# SguanFOC_MOTOR.net
KiCad netlist of a schematic drawn in EasyEDA Pro
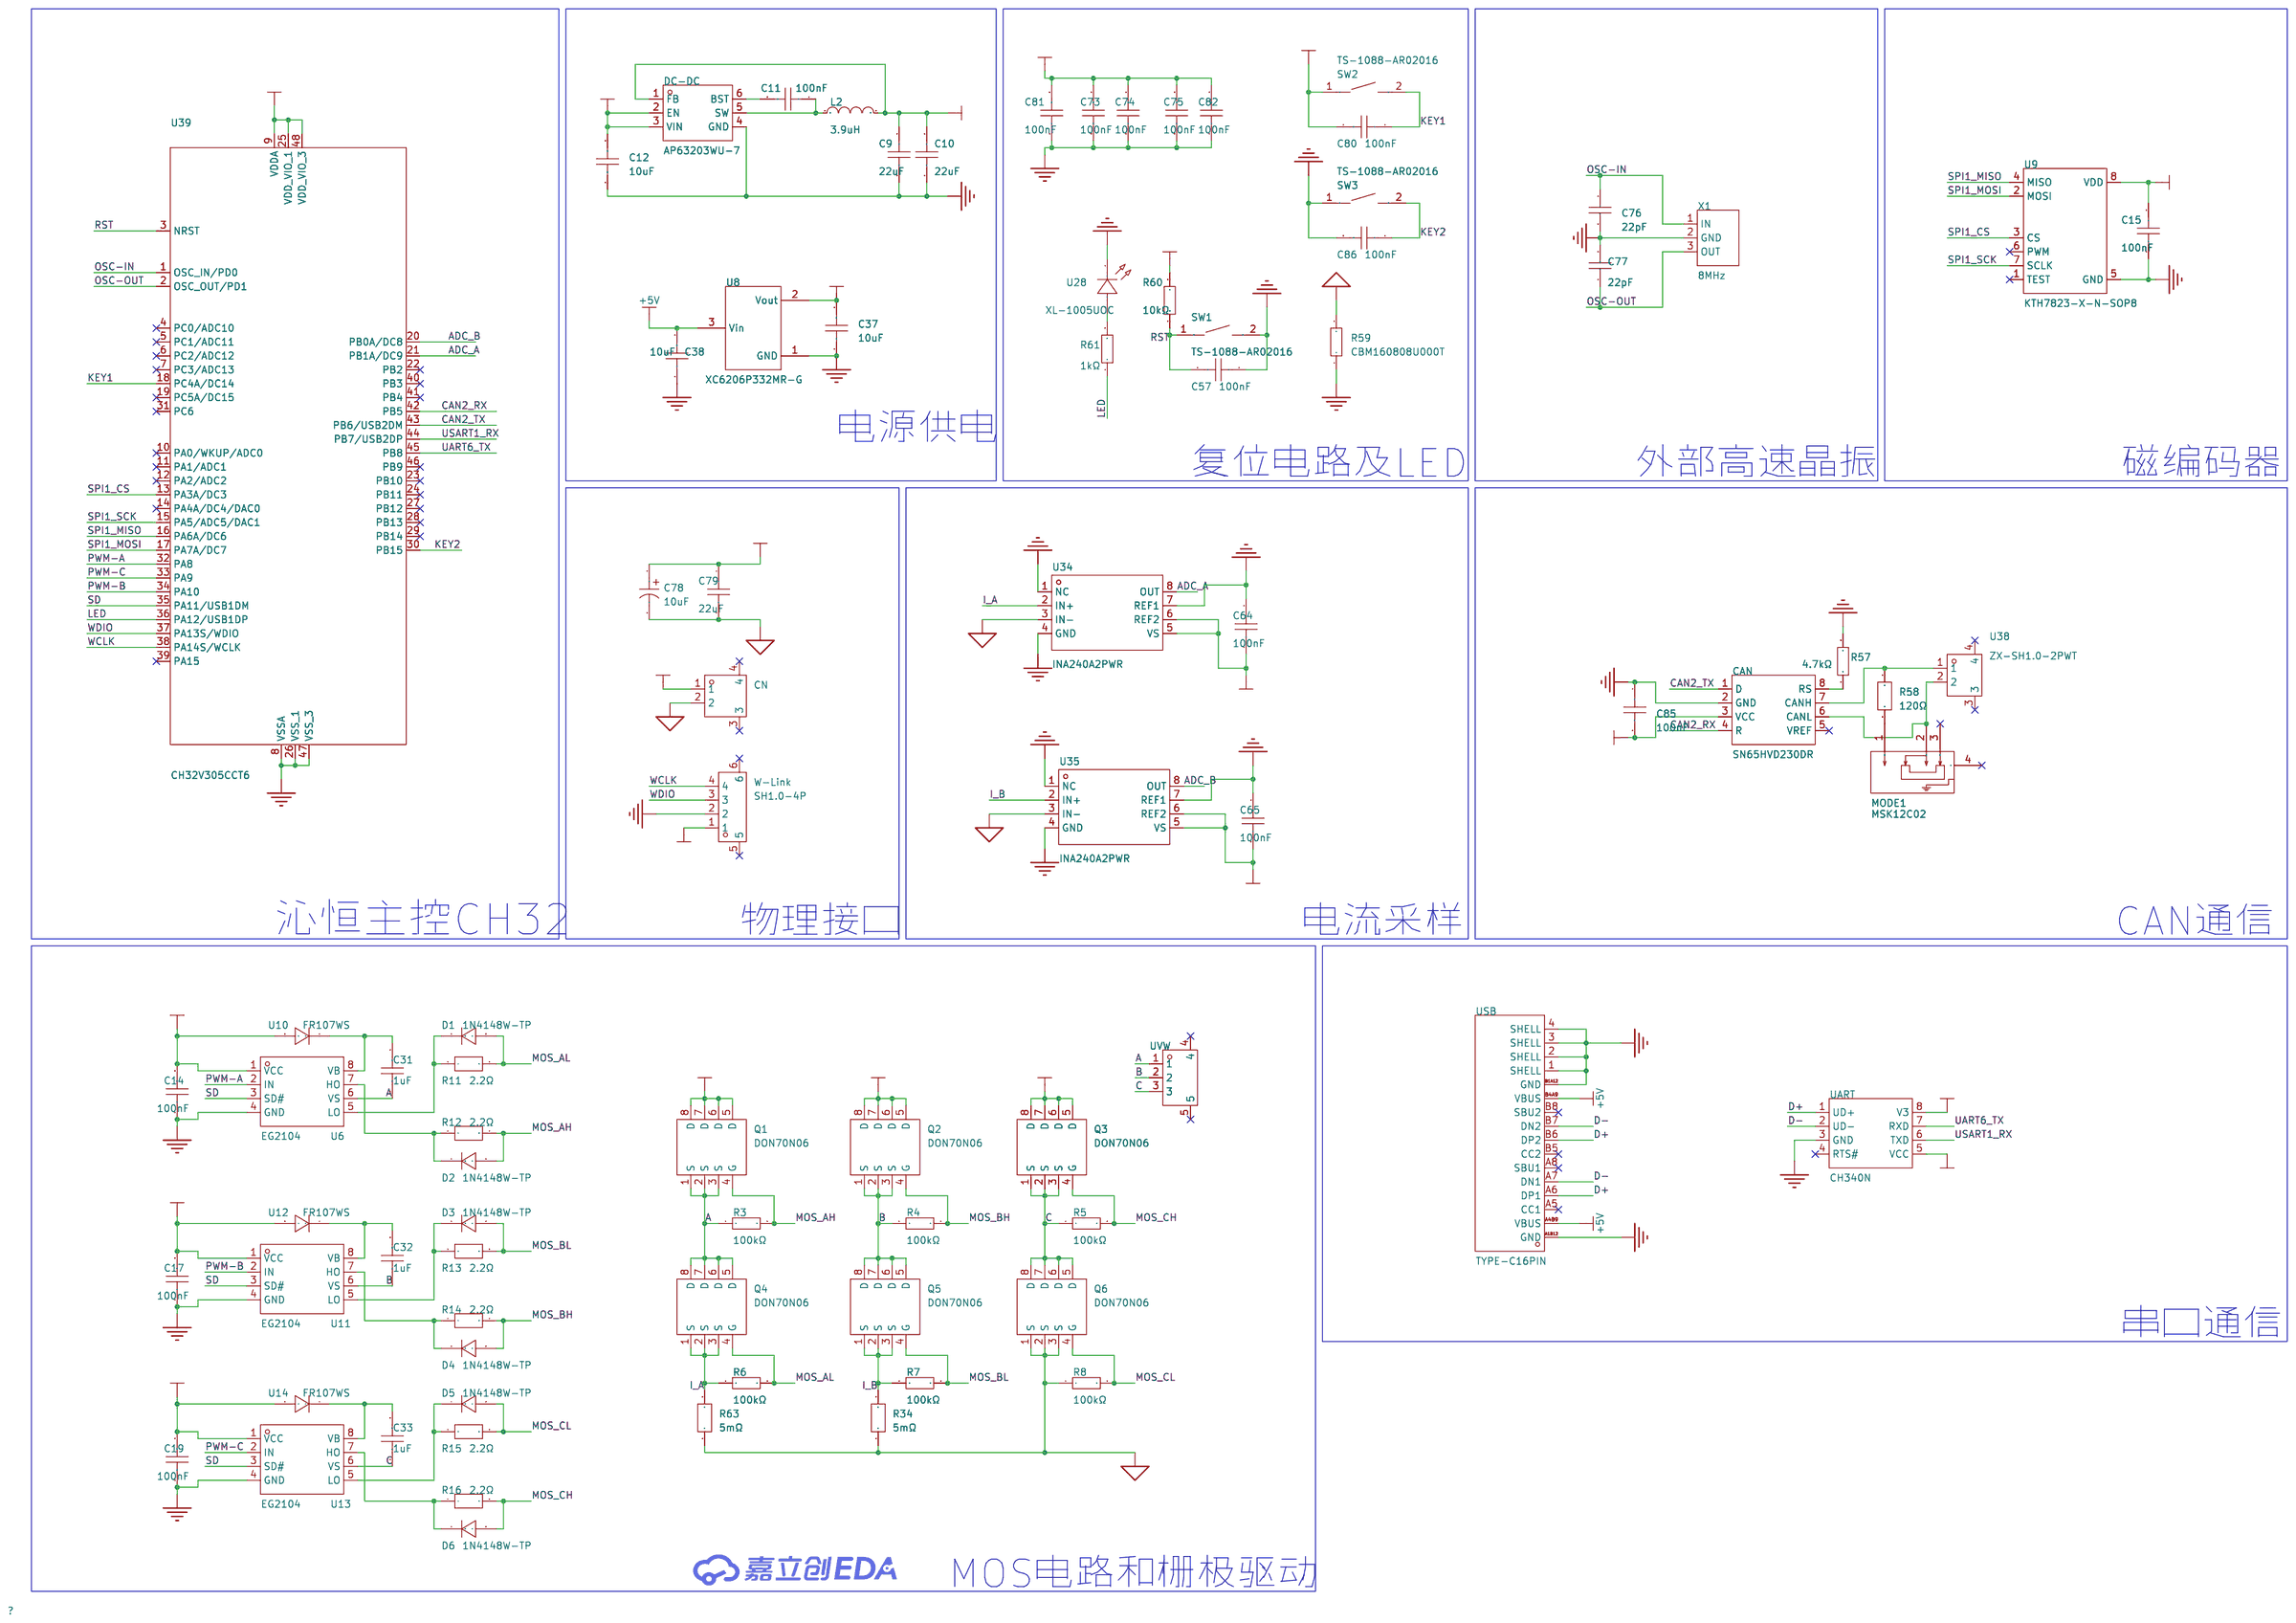
[diagram p0: schematic sheet]

(export (version "E")
  (design (tool "Eeschema 10.0.6"))
  (components
    (comp (ref "C9")
      (value "22uF")
      (footprint "easyedapro:C0603")
      (description "容值:22uF;精度:±20%;额定电压:10V;温度系数:X5R;")
      (fields
        (field (name "Manufacturer Part") "CGA0603X5R226M100JT")
        (field (name "Manufacturer") "HRE(芯声)")
      )
      (libsource (lib "easyedapro") (part "CGA0603X5R226M100JT"))
    )
    (comp (ref "C10")
      (value "22uF")
      (footprint "easyedapro:C0603")
      (description "容值:22uF;精度:±20%;额定电压:10V;温度系数:X5R;")
      (fields
        (field (name "Manufacturer Part") "CGA0603X5R226M100JT")
        (field (name "Manufacturer") "HRE(芯声)")
      )
      (libsource (lib "easyedapro") (part "CGA0603X5R226M100JT"))
    )
    (comp (ref "C11")
      (value "100nF")
      (footprint "easyedapro:C0603")
      (description "容值:100nF;精度:±10%;额定电压:50V;温度系数:X7R;")
      (fields
        (field (name "Manufacturer Part") "CGA0603X7R104K500JT")
        (field (name "Manufacturer") "HRE(芯声)")
      )
      (libsource (lib "easyedapro") (part "CGA0603X7R104K500JT"))
    )
    (comp (ref "C12")
      (value "10uF")
      (footprint "easyedapro:C0603")
      (description "容值:10uF;精度:±10%;额定电压:10V;温度系数:X5R;")
      (fields
        (field (name "Manufacturer Part") "CGA0603X5R106K100JT")
        (field (name "Manufacturer") "HRE(芯声)")
      )
      (libsource (lib "easyedapro") (part "CGA0603X5R106K100JT"))
    )
    (comp (ref "C14")
      (value "100nF")
      (footprint "easyedapro:C0603")
      (description "容值:100nF;精度:±10%;额定电压:50V;温度系数:X7R;")
      (fields
        (field (name "Manufacturer Part") "CGA0603X7R104K500JT")
        (field (name "Manufacturer") "HRE(芯声)")
      )
      (libsource (lib "easyedapro") (part "CGA0603X7R104K500JT"))
    )
    (comp (ref "C15")
      (value "100nF")
      (footprint "easyedapro:C0603")
      (description "容值:100nF;精度:±10%;额定电压:50V;温度系数:X7R;")
      (fields
        (field (name "Manufacturer Part") "CGA0603X7R104K500JT")
        (field (name "Manufacturer") "HRE(芯声)")
      )
      (libsource (lib "easyedapro") (part "CGA0603X7R104K500JT"))
    )
    (comp (ref "C17")
      (value "100nF")
      (footprint "easyedapro:C0603")
      (description "容值:100nF;精度:±10%;额定电压:50V;温度系数:X7R;")
      (fields
        (field (name "Manufacturer Part") "CGA0603X7R104K500JT")
        (field (name "Manufacturer") "HRE(芯声)")
      )
      (libsource (lib "easyedapro") (part "CGA0603X7R104K500JT"))
    )
    (comp (ref "C19")
      (value "100nF")
      (footprint "easyedapro:C0603")
      (description "容值:100nF;精度:±10%;额定电压:50V;温度系数:X7R;")
      (fields
        (field (name "Manufacturer Part") "CGA0603X7R104K500JT")
        (field (name "Manufacturer") "HRE(芯声)")
      )
      (libsource (lib "easyedapro") (part "CGA0603X7R104K500JT"))
    )
    (comp (ref "C31")
      (value "1uF")
      (footprint "easyedapro:C0603")
      (description "容值:1uF;精度:±10%;额定电压:50V;温度系数:X5R;")
      (fields
        (field (name "Manufacturer Part") "CGA0603X5R105K500JT")
        (field (name "Manufacturer") "HRE(芯声)")
      )
      (libsource (lib "easyedapro") (part "CGA0603X5R105K500JT"))
    )
    (comp (ref "C32")
      (value "1uF")
      (footprint "easyedapro:C0603")
      (description "容值:1uF;精度:±10%;额定电压:50V;温度系数:X5R;")
      (fields
        (field (name "Manufacturer Part") "CGA0603X5R105K500JT")
        (field (name "Manufacturer") "HRE(芯声)")
      )
      (libsource (lib "easyedapro") (part "CGA0603X5R105K500JT"))
    )
    (comp (ref "C33")
      (value "1uF")
      (footprint "easyedapro:C0603")
      (description "容值:1uF;精度:±10%;额定电压:50V;温度系数:X5R;")
      (fields
        (field (name "Manufacturer Part") "CGA0603X5R105K500JT")
        (field (name "Manufacturer") "HRE(芯声)")
      )
      (libsource (lib "easyedapro") (part "CGA0603X5R105K500JT"))
    )
    (comp (ref "C37")
      (value "10uF")
      (footprint "easyedapro:C0603")
      (libsource (lib "easyedapro") (part "Capacitance"))
    )
    (comp (ref "C38")
      (value "10uF")
      (footprint "easyedapro:C0603")
      (libsource (lib "easyedapro") (part "Capacitance"))
    )
    (comp (ref "C57")
      (value "100nF")
      (footprint "easyedapro:C0603")
      (description "容值:100nF;精度:±10%;额定电压:50V;温度系数:X7R;")
      (fields
        (field (name "Manufacturer Part") "CGA0603X7R104K500JT")
        (field (name "Manufacturer") "HRE(芯声)")
      )
      (libsource (lib "easyedapro") (part "CGA0603X7R104K500JT"))
    )
    (comp (ref "C64")
      (value "100nF")
      (footprint "easyedapro:C0603")
      (description "容值:100nF;精度:±10%;额定电压:50V;温度系数:X7R;")
      (fields
        (field (name "Manufacturer Part") "CGA0603X7R104K500JT")
        (field (name "Manufacturer") "HRE(芯声)")
      )
      (libsource (lib "easyedapro") (part "CGA0603X7R104K500JT"))
    )
    (comp (ref "C65")
      (value "100nF")
      (footprint "easyedapro:C0603")
      (description "容值:100nF;精度:±10%;额定电压:50V;温度系数:X7R;")
      (fields
        (field (name "Manufacturer Part") "CGA0603X7R104K500JT")
        (field (name "Manufacturer") "HRE(芯声)")
      )
      (libsource (lib "easyedapro") (part "CGA0603X7R104K500JT"))
    )
    (comp (ref "C73")
      (value "100nF")
      (footprint "easyedapro:C0603")
      (description "容值:100nF;精度:±10%;额定电压:50V;温度系数:X7R;")
      (fields
        (field (name "Manufacturer Part") "CGA0603X7R104K500JT")
        (field (name "Manufacturer") "HRE(芯声)")
      )
      (libsource (lib "easyedapro") (part "CGA0603X7R104K500JT"))
    )
    (comp (ref "C74")
      (value "100nF")
      (footprint "easyedapro:C0603")
      (description "容值:100nF;精度:±10%;额定电压:50V;温度系数:X7R;")
      (fields
        (field (name "Manufacturer Part") "CGA0603X7R104K500JT")
        (field (name "Manufacturer") "HRE(芯声)")
      )
      (libsource (lib "easyedapro") (part "CGA0603X7R104K500JT"))
    )
    (comp (ref "C75")
      (value "100nF")
      (footprint "easyedapro:C0603")
      (description "容值:100nF;精度:±10%;额定电压:50V;温度系数:X7R;")
      (fields
        (field (name "Manufacturer Part") "CGA0603X7R104K500JT")
        (field (name "Manufacturer") "HRE(芯声)")
      )
      (libsource (lib "easyedapro") (part "CGA0603X7R104K500JT"))
    )
    (comp (ref "C76")
      (value "22pF")
      (footprint "easyedapro:C0603")
      (description "容值:22pF;精度:±5%;额定电压:50V;温度系数:C0G;")
      (fields
        (field (name "Manufacturer Part") "CL10C220JB8NNNC")
        (field (name "Manufacturer") "SAMSUNG(三星)")
      )
      (libsource (lib "easyedapro") (part "CL10C220JB8NNNC"))
    )
    (comp (ref "C77")
      (value "22pF")
      (footprint "easyedapro:C0603")
      (description "容值:22pF;精度:±5%;额定电压:50V;温度系数:C0G;")
      (fields
        (field (name "Manufacturer Part") "CL10C220JB8NNNC")
        (field (name "Manufacturer") "SAMSUNG(三星)")
      )
      (libsource (lib "easyedapro") (part "CL10C220JB8NNNC"))
    )
    (comp (ref "C78")
      (value "10uF")
      (footprint "easyedapro:CAP-SMD_BD4.0-L4.3-W4.3-LS5.1-FD")
      (description "容值:10uF;精度:±20%;额定电压:25V;纹波电流:14mA@120Hz;等效串联电阻(ESR):-;")
      (fields (field (name "Manufacturer Part") "RVT16V10M4X5") (field (name "Manufacturer") "JIERR(捷而瑞)"))
      (libsource (lib "easyedapro") (part "JVJ25V10M4X6"))
    )
    (comp (ref "C79")
      (value "22uF")
      (footprint "easyedapro:C0603")
      (description "容值:22uF;精度:±20%;额定电压:10V;温度系数:X5R;")
      (fields
        (field (name "Manufacturer Part") "CGA0603X5R226M100JT")
        (field (name "Manufacturer") "HRE(芯声)")
      )
      (libsource (lib "easyedapro") (part "CGA0603X5R226M100JT"))
    )
    (comp (ref "C80")
      (value "100nF")
      (footprint "easyedapro:C0603")
      (description "容值:100nF;精度:±10%;额定电压:50V;温度系数:X7R;")
      (fields
        (field (name "Manufacturer Part") "CGA0603X7R104K500JT")
        (field (name "Manufacturer") "HRE(芯声)")
      )
      (libsource (lib "easyedapro") (part "CGA0603X7R104K500JT"))
    )
    (comp (ref "C81")
      (value "100nF")
      (footprint "easyedapro:C0603")
      (description "容值:100nF;精度:±10%;额定电压:50V;温度系数:X7R;")
      (fields
        (field (name "Manufacturer Part") "CGA0603X7R104K500JT")
        (field (name "Manufacturer") "HRE(芯声)")
      )
      (libsource (lib "easyedapro") (part "CGA0603X7R104K500JT"))
    )
    (comp (ref "C82")
      (value "100nF")
      (footprint "easyedapro:C0603")
      (description "容值:100nF;精度:±10%;额定电压:50V;温度系数:X7R;")
      (fields
        (field (name "Manufacturer Part") "CGA0603X7R104K500JT")
        (field (name "Manufacturer") "HRE(芯声)")
      )
      (libsource (lib "easyedapro") (part "CGA0603X7R104K500JT"))
    )
    (comp (ref "C85")
      (value "100nF")
      (footprint "easyedapro:C0603")
      (description "容值:100nF;精度:±10%;额定电压:50V;温度系数:X7R;")
      (fields
        (field (name "Manufacturer Part") "CGA0603X7R104K500JT")
        (field (name "Manufacturer") "HRE(芯声)")
      )
      (libsource (lib "easyedapro") (part "CGA0603X7R104K500JT"))
    )
    (comp (ref "C86")
      (value "100nF")
      (footprint "easyedapro:C0603")
      (description "容值:100nF;精度:±10%;额定电压:50V;温度系数:X7R;")
      (fields
        (field (name "Manufacturer Part") "CGA0603X7R104K500JT")
        (field (name "Manufacturer") "HRE(芯声)")
      )
      (libsource (lib "easyedapro") (part "CGA0603X7R104K500JT"))
    )
    (comp (ref "CAN")
      (value "SN65HVD230DR")
      (footprint "easyedapro:SOIC-8_L4.9-W3.9-P1.27-LS6.0-BL")
      (description "类型:CAN收发器;数据速率:1Mbps;")
      (fields (field (name "Manufacturer") "TI(德州仪器)"))
      (libsource (lib "easyedapro") (part "SN65HVD230DR"))
    )
    (comp (ref "CN")
      (value "XT30PW-M")
      (footprint "easyedapro:CONN-TH_XT30PW-M")
      (description "Socket,DCsupply,XT30,male,PIN:2")
      (fields (field (name "Manufacturer") "AMASS(艾迈斯)"))
      (libsource (lib "easyedapro") (part "XT30PW-M"))
    )
    (comp (ref "D1")
      (value "1N4148W-TP")
      (footprint "easyedapro:SOD-123_L2.8-W1.8-LS3.7-RD")
      (description "二极管配置:-;正向压降(Vf):1.25V@150mA;直流反向耐压(Vr):100V;整流电流:150mA;反向恢复时间(Trr):4ns;")
      (fields (field (name "Manufacturer") "MCC(美微科)"))
      (libsource (lib "easyedapro") (part "1N4148W-TP"))
    )
    (comp (ref "D2")
      (value "1N4148W-TP")
      (footprint "easyedapro:SOD-123_L2.8-W1.8-LS3.7-RD")
      (description "二极管配置:-;正向压降(Vf):1.25V@150mA;直流反向耐压(Vr):100V;整流电流:150mA;反向恢复时间(Trr):4ns;")
      (fields (field (name "Manufacturer") "MCC(美微科)"))
      (libsource (lib "easyedapro") (part "1N4148W-TP"))
    )
    (comp (ref "D3")
      (value "1N4148W-TP")
      (footprint "easyedapro:SOD-123_L2.8-W1.8-LS3.7-RD")
      (description "二极管配置:-;正向压降(Vf):1.25V@150mA;直流反向耐压(Vr):100V;整流电流:150mA;反向恢复时间(Trr):4ns;")
      (fields (field (name "Manufacturer") "MCC(美微科)"))
      (libsource (lib "easyedapro") (part "1N4148W-TP"))
    )
    (comp (ref "D4")
      (value "1N4148W-TP")
      (footprint "easyedapro:SOD-123_L2.8-W1.8-LS3.7-RD")
      (description "二极管配置:-;正向压降(Vf):1.25V@150mA;直流反向耐压(Vr):100V;整流电流:150mA;反向恢复时间(Trr):4ns;")
      (fields (field (name "Manufacturer") "MCC(美微科)"))
      (libsource (lib "easyedapro") (part "1N4148W-TP"))
    )
    (comp (ref "D5")
      (value "1N4148W-TP")
      (footprint "easyedapro:SOD-123_L2.8-W1.8-LS3.7-RD")
      (description "二极管配置:-;正向压降(Vf):1.25V@150mA;直流反向耐压(Vr):100V;整流电流:150mA;反向恢复时间(Trr):4ns;")
      (fields (field (name "Manufacturer") "MCC(美微科)"))
      (libsource (lib "easyedapro") (part "1N4148W-TP"))
    )
    (comp (ref "D6")
      (value "1N4148W-TP")
      (footprint "easyedapro:SOD-123_L2.8-W1.8-LS3.7-RD")
      (description "二极管配置:-;正向压降(Vf):1.25V@150mA;直流反向耐压(Vr):100V;整流电流:150mA;反向恢复时间(Trr):4ns;")
      (fields (field (name "Manufacturer") "MCC(美微科)"))
      (libsource (lib "easyedapro") (part "1N4148W-TP"))
    )
    (comp (ref "DC-DC")
      (value "AP63203WU-7")
      (footprint "easyedapro:TSOT-26_L2.9-W1.6-P0.95-LS2.8-BL")
      (description "功能类型:降压型;工作电压:3.8V~32V;输出电压:3.3V;输出电流:2A;输出类型:固定;")
      (fields (field (name "Manufacturer") "DIODES(美台)"))
      (libsource (lib "easyedapro") (part "AP63203WU-7"))
    )
    (comp (ref "L2")
      (value "3.9uH")
      (footprint "easyedapro:IND-SMD_L3.0-W3.0_FNR30XXS")
      (description "电感值:3.9uH;精度:±20%;额定电流:1.5A;饱和电流(Isat):1.4A;类型:磁胶屏蔽绕线合金电感;")
      (fields (field (name "Manufacturer Part") "FNR3015S3R9MT") (field (name "Manufacturer") "cjiang(长江微电)"))
      (libsource (lib "easyedapro") (part "FNR3015S3R9MT"))
    )
    (comp (ref "MODE1")
      (value "MSK12C02")
      (footprint "easyedapro:SW-TH_MSK12C02")
      (description "电路结构:单刀双掷;安装方式:卧贴;开关颜色:-;额定电流(DC):50mA;额定电压(DC):12V;额定电流(AC):-;额定电压(AC):-;机械寿命:1万次;")
      (fields (field (name "Manufacturer") "SHOU HAN(首韩)"))
      (libsource (lib "easyedapro") (part "MSK12C02"))
    )
    (comp (ref "Q1")
      (value "DON70N06")
      (footprint "easyedapro:DFN-8_L5.8-W4.9-P1.27-LS6.1-BL-2")
      (fields (field (name "Manufacturer") "DOINGTER(杜因特)"))
      (libsource (lib "easyedapro") (part "DON70N06"))
    )
    (comp (ref "Q2")
      (value "DON70N06")
      (footprint "easyedapro:DFN-8_L5.8-W4.9-P1.27-LS6.1-BL-2")
      (fields (field (name "Manufacturer") "DOINGTER(杜因特)"))
      (libsource (lib "easyedapro") (part "DON70N06"))
    )
    (comp (ref "Q3")
      (value "DON70N06")
      (footprint "easyedapro:DFN-8_L5.8-W4.9-P1.27-LS6.1-BL-2")
      (fields (field (name "Manufacturer") "DOINGTER(杜因特)"))
      (libsource (lib "easyedapro") (part "DON70N06"))
    )
    (comp (ref "Q4")
      (value "DON70N06")
      (footprint "easyedapro:DFN-8_L5.8-W4.9-P1.27-LS6.1-BL-2")
      (fields (field (name "Manufacturer") "DOINGTER(杜因特)"))
      (libsource (lib "easyedapro") (part "DON70N06"))
    )
    (comp (ref "Q5")
      (value "DON70N06")
      (footprint "easyedapro:DFN-8_L5.8-W4.9-P1.27-LS6.1-BL-2")
      (fields (field (name "Manufacturer") "DOINGTER(杜因特)"))
      (libsource (lib "easyedapro") (part "DON70N06"))
    )
    (comp (ref "Q6")
      (value "DON70N06")
      (footprint "easyedapro:DFN-8_L5.8-W4.9-P1.27-LS6.1-BL-2")
      (fields (field (name "Manufacturer") "DOINGTER(杜因特)"))
      (libsource (lib "easyedapro") (part "DON70N06"))
    )
    (comp (ref "R3")
      (value "100kΩ")
      (footprint "easyedapro:R0603")
      (description "电阻类型:厚膜电阻;阻值:100kΩ;精度:±1%;功率:100mW;工作电压:75V;温度系数:±100ppm/°C;")
      (fields
        (field (name "Manufacturer Part") "0603WAF1003T5E")
        (field (name "Manufacturer") "UNI-ROYAL(厚声)")
      )
      (libsource (lib "easyedapro") (part "0603WAF1003T5E"))
    )
    (comp (ref "R4")
      (value "100kΩ")
      (footprint "easyedapro:R0603")
      (description "电阻类型:厚膜电阻;阻值:100kΩ;精度:±1%;功率:100mW;工作电压:75V;温度系数:±100ppm/°C;")
      (fields
        (field (name "Manufacturer Part") "0603WAF1003T5E")
        (field (name "Manufacturer") "UNI-ROYAL(厚声)")
      )
      (libsource (lib "easyedapro") (part "0603WAF1003T5E"))
    )
    (comp (ref "R5")
      (value "100kΩ")
      (footprint "easyedapro:R0603")
      (description "电阻类型:厚膜电阻;阻值:100kΩ;精度:±1%;功率:100mW;工作电压:75V;温度系数:±100ppm/°C;")
      (fields
        (field (name "Manufacturer Part") "0603WAF1003T5E")
        (field (name "Manufacturer") "UNI-ROYAL(厚声)")
      )
      (libsource (lib "easyedapro") (part "0603WAF1003T5E"))
    )
    (comp (ref "R6")
      (value "100kΩ")
      (footprint "easyedapro:R0603")
      (description "电阻类型:厚膜电阻;阻值:100kΩ;精度:±1%;功率:100mW;工作电压:75V;温度系数:±100ppm/°C;")
      (fields
        (field (name "Manufacturer Part") "0603WAF1003T5E")
        (field (name "Manufacturer") "UNI-ROYAL(厚声)")
      )
      (libsource (lib "easyedapro") (part "0603WAF1003T5E"))
    )
    (comp (ref "R7")
      (value "100kΩ")
      (footprint "easyedapro:R0603")
      (description "电阻类型:厚膜电阻;阻值:100kΩ;精度:±1%;功率:100mW;工作电压:75V;温度系数:±100ppm/°C;")
      (fields
        (field (name "Manufacturer Part") "0603WAF1003T5E")
        (field (name "Manufacturer") "UNI-ROYAL(厚声)")
      )
      (libsource (lib "easyedapro") (part "0603WAF1003T5E"))
    )
    (comp (ref "R8")
      (value "100kΩ")
      (footprint "easyedapro:R0603")
      (description "电阻类型:厚膜电阻;阻值:100kΩ;精度:±1%;功率:100mW;工作电压:75V;温度系数:±100ppm/°C;")
      (fields
        (field (name "Manufacturer Part") "0603WAF1003T5E")
        (field (name "Manufacturer") "UNI-ROYAL(厚声)")
      )
      (libsource (lib "easyedapro") (part "0603WAF1003T5E"))
    )
    (comp (ref "R11")
      (value "2.2Ω")
      (footprint "easyedapro:R1206")
      (description "电阻类型:厚膜电阻;阻值:2.2Ω;精度:±5%;功率:250mW;工作电压:200V;温度系数:±200ppm/°C;")
      (fields (field (name "Manufacturer Part") "FRC1206J2R2 TS") (field (name "Manufacturer") "FOJAN(富捷)"))
      (libsource (lib "easyedapro") (part "FRC1206J2R2 TS"))
    )
    (comp (ref "R12")
      (value "2.2Ω")
      (footprint "easyedapro:R1206")
      (description "电阻类型:厚膜电阻;阻值:2.2Ω;精度:±5%;功率:250mW;工作电压:200V;温度系数:±200ppm/°C;")
      (fields (field (name "Manufacturer Part") "FRC1206J2R2 TS") (field (name "Manufacturer") "FOJAN(富捷)"))
      (libsource (lib "easyedapro") (part "FRC1206J2R2 TS"))
    )
    (comp (ref "R13")
      (value "2.2Ω")
      (footprint "easyedapro:R1206")
      (description "电阻类型:厚膜电阻;阻值:2.2Ω;精度:±5%;功率:250mW;工作电压:200V;温度系数:±200ppm/°C;")
      (fields (field (name "Manufacturer Part") "FRC1206J2R2 TS") (field (name "Manufacturer") "FOJAN(富捷)"))
      (libsource (lib "easyedapro") (part "FRC1206J2R2 TS"))
    )
    (comp (ref "R14")
      (value "2.2Ω")
      (footprint "easyedapro:R1206")
      (description "电阻类型:厚膜电阻;阻值:2.2Ω;精度:±5%;功率:250mW;工作电压:200V;温度系数:±200ppm/°C;")
      (fields (field (name "Manufacturer Part") "FRC1206J2R2 TS") (field (name "Manufacturer") "FOJAN(富捷)"))
      (libsource (lib "easyedapro") (part "FRC1206J2R2 TS"))
    )
    (comp (ref "R15")
      (value "2.2Ω")
      (footprint "easyedapro:R1206")
      (description "电阻类型:厚膜电阻;阻值:2.2Ω;精度:±5%;功率:250mW;工作电压:200V;温度系数:±200ppm/°C;")
      (fields (field (name "Manufacturer Part") "FRC1206J2R2 TS") (field (name "Manufacturer") "FOJAN(富捷)"))
      (libsource (lib "easyedapro") (part "FRC1206J2R2 TS"))
    )
    (comp (ref "R16")
      (value "2.2Ω")
      (footprint "easyedapro:R1206")
      (description "电阻类型:厚膜电阻;阻值:2.2Ω;精度:±5%;功率:250mW;工作电压:200V;温度系数:±200ppm/°C;")
      (fields (field (name "Manufacturer Part") "FRC1206J2R2 TS") (field (name "Manufacturer") "FOJAN(富捷)"))
      (libsource (lib "easyedapro") (part "FRC1206J2R2 TS"))
    )
    (comp (ref "R34")
      (value "5mΩ")
      (footprint "easyedapro:R2512")
      (description "电阻类型:采样电阻；合金电阻;阻值:5mΩ;精度:±1%;功率:3W;温度系数:±50ppm/°C;")
      (fields (field (name "Manufacturer Part") "JER2512F3R005") (field (name "Manufacturer") "JIERR(捷而瑞)"))
      (libsource (lib "easyedapro") (part "JER2512F3R005"))
    )
    (comp (ref "R57")
      (value "4.7kΩ")
      (footprint "easyedapro:R0603")
      (description "电阻类型:厚膜电阻;阻值:4.7kΩ;精度:±1%;功率:100mW;工作电压:75V;温度系数:±100ppm/°C;")
      (fields
        (field (name "Manufacturer Part") "0603WAF4701T5E")
        (field (name "Manufacturer") "UNI-ROYAL(厚声)")
      )
      (libsource (lib "easyedapro") (part "0603WAF4701T5E"))
    )
    (comp (ref "R58")
      (value "120Ω")
      (footprint "easyedapro:R0603")
      (description "电阻类型:厚膜电阻;阻值:120Ω;精度:±5%;功率:100mW;工作电压:75V;温度系数:±100ppm/°C;")
      (fields (field (name "Manufacturer Part") "FRC0603J121 TS") (field (name "Manufacturer") "FOJAN(富捷)"))
      (libsource (lib "easyedapro") (part "FRC0603J121 TS"))
    )
    (comp (ref "R59")
      (value "CBM160808U000T")
      (footprint "easyedapro:R0603")
      (description "电阻类型:厚膜电阻;阻值:0Ω;精度:±1%;功率:100mW;工作电压:75V;温度系数:-;")
      (fields (field (name "Manufacturer") "FH(风华)"))
      (libsource (lib "easyedapro") (part "0603WAF0000T5E"))
    )
    (comp (ref "R60")
      (value "10kΩ")
      (footprint "easyedapro:R0603")
      (description "电阻类型:厚膜电阻;阻值:10kΩ;精度:±1%;功率:100mW;工作电压:75V;温度系数:±100ppm/°C;")
      (fields
        (field (name "Manufacturer Part") "0603WAF1002T5E")
        (field (name "Manufacturer") "UNI-ROYAL(厚声)")
      )
      (libsource (lib "easyedapro") (part "0603WAF1002T5E"))
    )
    (comp (ref "R61")
      (value "1kΩ")
      (footprint "easyedapro:R0603")
      (description "电阻类型:厚膜电阻;阻值:1kΩ;精度:±1%;功率:100mW;工作电压:75V;温度系数:±100ppm/°C;")
      (fields
        (field (name "Manufacturer Part") "0603WAF1001T5E")
        (field (name "Manufacturer") "UNI-ROYAL(厚声)")
      )
      (libsource (lib "easyedapro") (part "0603WAF1001T5E"))
    )
    (comp (ref "R63")
      (value "5mΩ")
      (footprint "easyedapro:R2512")
      (description "电阻类型:采样电阻；合金电阻;阻值:5mΩ;精度:±1%;功率:3W;温度系数:±50ppm/°C;")
      (fields (field (name "Manufacturer Part") "JER2512F3R005") (field (name "Manufacturer") "JIERR(捷而瑞)"))
      (libsource (lib "easyedapro") (part "JER2512F3R005"))
    )
    (comp (ref "SW1")
      (value "TS-1088-AR02016")
      (footprint "easyedapro:SW-SMD_L3.9-W3.0-P4.45")
      (fields (field (name "Manufacturer") "XUNPU(讯普)"))
      (libsource (lib "easyedapro") (part "TS-1088-AR02016"))
    )
    (comp (ref "SW2")
      (value "TS-1088-AR02016")
      (footprint "easyedapro:SW-SMD_L3.9-W3.0-P4.45")
      (fields (field (name "Manufacturer") "XUNPU(讯普)"))
      (libsource (lib "easyedapro") (part "TS-1088-AR02016"))
    )
    (comp (ref "SW3")
      (value "TS-1088-AR02016")
      (footprint "easyedapro:SW-SMD_L3.9-W3.0-P4.45")
      (fields (field (name "Manufacturer") "XUNPU(讯普)"))
      (libsource (lib "easyedapro") (part "TS-1088-AR02016"))
    )
    (comp (ref "U6")
      (value "EG2104")
      (footprint "easyedapro:SOP-8_L5.0-W4.0-P1.27-LS6.2-BL")
      (description "高性价比, 600V，半桥式Nmos预驱动器")
      (fields (field (name "Manufacturer") "EG(屹晶微)"))
      (libsource (lib "easyedapro") (part "EG2104"))
    )
    (comp (ref "U8")
      (value "XC6206P332MR-G")
      (footprint "easyedapro:SOT-23-3_L2.9-W1.6-P1.90-LS2.8-BR")
      (description "输出类型:固定;工作电压:6V;输出电压:3.3V;输出电流:200mA;电源纹波抑制比(PSRR):-;输出极性:正极;")
      (fields (field (name "Manufacturer") "TOREX(特瑞仕)"))
      (libsource (lib "easyedapro") (part "XC6206P332MR"))
    )
    (comp (ref "U9")
      (value "KTH7823-X-N-SOP8")
      (footprint "easyedapro:SOP-8_L4.9-W3.9-P1.27-LS6.0-BL")
      (fields (field (name "Manufacturer") "CONNTEK(昆泰芯)"))
      (libsource (lib "easyedapro") (part "KTH7823-X-N-SOP8"))
    )
    (comp (ref "U10")
      (value "FR107WS")
      (footprint "easyedapro:SOD-323_L1.6-W1.3-LS2.7-RD")
      (description "二极管配置:独立式;正向压降(Vf):1.3V@1A;直流反向耐压(Vr):1kV;整流电流:1A;反向恢复时间(Trr):500ns;")
      (fields (field (name "Manufacturer") "MDD(辰达半导体)"))
      (libsource (lib "easyedapro") (part "FR107WS"))
    )
    (comp (ref "U11")
      (value "EG2104")
      (footprint "easyedapro:SOP-8_L5.0-W4.0-P1.27-LS6.2-BL")
      (description "高性价比, 600V，半桥式Nmos预驱动器")
      (fields (field (name "Manufacturer") "EG(屹晶微)"))
      (libsource (lib "easyedapro") (part "EG2104"))
    )
    (comp (ref "U12")
      (value "FR107WS")
      (footprint "easyedapro:SOD-323_L1.6-W1.3-LS2.7-RD")
      (description "二极管配置:独立式;正向压降(Vf):1.3V@1A;直流反向耐压(Vr):1kV;整流电流:1A;反向恢复时间(Trr):500ns;")
      (fields (field (name "Manufacturer") "MDD(辰达半导体)"))
      (libsource (lib "easyedapro") (part "FR107WS"))
    )
    (comp (ref "U13")
      (value "EG2104")
      (footprint "easyedapro:SOP-8_L5.0-W4.0-P1.27-LS6.2-BL")
      (description "高性价比, 600V，半桥式Nmos预驱动器")
      (fields (field (name "Manufacturer") "EG(屹晶微)"))
      (libsource (lib "easyedapro") (part "EG2104"))
    )
    (comp (ref "U14")
      (value "FR107WS")
      (footprint "easyedapro:SOD-323_L1.6-W1.3-LS2.7-RD")
      (description "二极管配置:独立式;正向压降(Vf):1.3V@1A;直流反向耐压(Vr):1kV;整流电流:1A;反向恢复时间(Trr):500ns;")
      (fields (field (name "Manufacturer") "MDD(辰达半导体)"))
      (libsource (lib "easyedapro") (part "FR107WS"))
    )
    (comp (ref "U28")
      (value "XL-1005UOC")
      (footprint "easyedapro:LED0402-RD_ORANGE")
      (fields (field (name "Manufacturer") "XINGLIGHT(成兴光)"))
      (libsource (lib "easyedapro") (part "XL-1005UOC"))
    )
    (comp (ref "U34")
      (value "INA240A2PWR")
      (footprint "easyedapro:TSSOP-8_L4.4-W3.0-P0.65-LS6.4-BL")
      (description "放大器数:单路;共模电压:-4V~80V;增益:50V/V;带宽:400kHz;")
      (fields (field (name "Manufacturer") "TI(德州仪器)"))
      (libsource (lib "easyedapro") (part "INA240A2PWR"))
    )
    (comp (ref "U35")
      (value "INA240A2PWR")
      (footprint "easyedapro:TSSOP-8_L4.4-W3.0-P0.65-LS6.4-BL")
      (description "放大器数:单路;共模电压:-4V~80V;增益:50V/V;带宽:400kHz;")
      (fields (field (name "Manufacturer") "TI(德州仪器)"))
      (libsource (lib "easyedapro") (part "INA240A2PWR"))
    )
    (comp (ref "U38")
      (value "ZX-SH1.0-2PWT")
      (footprint "easyedapro:CONN-SMD_2P-P1.00_HX-1.0-2P-WT")
      (fields (field (name "Manufacturer") "Megastar(兆星)"))
      (libsource (lib "easyedapro") (part "ZX-SH1.0-2PWT"))
    )
    (comp (ref "U39")
      (value "CH32V305CCT6")
      (footprint "easyedapro:LQFP-48_L7.0-W7.0-P0.50-LS9.0-BL_1")
      (libsource (lib "easyedapro") (part "CH32V305CCT6"))
    )
    (comp (ref "UART")
      (value "CH340N")
      (footprint "easyedapro:SOP-8_L4.9-W3.9-P1.27-LS6.0-BL")
      (description "应用功能:USB转串口;接口协议:USB 2.0;通道数:1;数据速率:2Mbps;")
      (fields (field (name "Manufacturer") "WCH(南京沁恒)"))
      (libsource (lib "easyedapro") (part "CH340N_C2977777"))
    )
    (comp (ref "USB")
      (value "TYPE-C16PIN")
      (footprint "easyedapro:USB-C-SMD_TYPE-C16PIN")
      (description "连接器类型:Type-C;协议标准:USB 3.1;公母:母;安装方式:卧贴;触点数量:16P;端口数量:1;额定电流 - 电源:3A;工作温度:-40°C~+85°C;")
      (fields (field (name "Manufacturer") "SHOU HAN(首韩)"))
      (libsource (lib "easyedapro") (part "TYPE-C16PIN"))
    )
    (comp (ref "UVW")
      (value "MR30PW-F")
      (footprint "easyedapro:CONN-TH_MR30PW-F")
      (libsource (lib "easyedapro") (part "MR30PW-F"))
    )
    (comp (ref "W-Link")
      (value "SH1.0-4P")
      (footprint "easyedapro:CONN-SMD_4P-P1.00_SH1.0-4P")
      (libsource (lib "easyedapro") (part "SH1.0-4P"))
    )
    (comp (ref "X1")
      (value "8MHz")
      (footprint "easyedapro:OSC-SMD_3P-L3.2-W1.3-P1.20")
      (description "频率:8MHz;内置负载电容:10pF;谐振阻抗:40Ω;")
      (fields
        (field (name "Manufacturer Part") "CSTNE8M00G520000R0")
        (field (name "Manufacturer") "muRata(村田)")
      )
      (libsource (lib "easyedapro") (part "CSTNE8M00G520000R0"))
    )
  )
  (nets
    (net (code "1") (name "+3.3V") (class "Default")
      (node (ref "C10") (pin "1") (pinfunction "1_1") (pintype "unspecified"))
      (node (ref "C15") (pin "2") (pinfunction "2_2") (pintype "unspecified"))
      (node (ref "C37") (pin "2") (pinfunction "2_2") (pintype "input"))
      (node (ref "C64") (pin "1") (pinfunction "1_1") (pintype "unspecified"))
      (node (ref "C65") (pin "1") (pinfunction "1_1") (pintype "unspecified"))
      (node (ref "C73") (pin "2") (pinfunction "2_2") (pintype "unspecified"))
      (node (ref "C74") (pin "2") (pinfunction "2_2") (pintype "unspecified"))
      (node (ref "C75") (pin "2") (pinfunction "2_2") (pintype "unspecified"))
      (node (ref "C80") (pin "2") (pinfunction "2_2") (pintype "unspecified"))
      (node (ref "C81") (pin "2") (pinfunction "2_2") (pintype "unspecified"))
      (node (ref "C82") (pin "2") (pinfunction "2_2") (pintype "unspecified"))
      (node (ref "C85") (pin "2") (pinfunction "2_2") (pintype "unspecified"))
      (node (ref "C9") (pin "1") (pinfunction "1_1") (pintype "unspecified"))
      (node (ref "CAN") (pin "3") (pinfunction "VCC_3") (pintype "unspecified"))
      (node (ref "DC-DC") (pin "1") (pinfunction "FB_1") (pintype "unspecified"))
      (node (ref "L2") (pin "2") (pinfunction "2_2") (pintype "unspecified"))
      (node (ref "R60") (pin "1") (pinfunction "1_1") (pintype "input"))
      (node (ref "SW2") (pin "1") (pinfunction "1_1") (pintype "unspecified"))
      (node (ref "U34") (pin "5") (pinfunction "VS_5") (pintype "unspecified"))
      (node (ref "U34") (pin "6") (pinfunction "REF2_6") (pintype "unspecified"))
      (node (ref "U35") (pin "5") (pinfunction "VS_5") (pintype "unspecified"))
      (node (ref "U35") (pin "6") (pinfunction "REF2_6") (pintype "unspecified"))
      (node (ref "U39") (pin "25") (pinfunction "VDD_VIO_1_25") (pintype "unspecified"))
      (node (ref "U39") (pin "48") (pinfunction "VDD_VIO_3_48") (pintype "unspecified"))
      (node (ref "U39") (pin "9") (pinfunction "VDDA_9") (pintype "unspecified"))
      (node (ref "U8") (pin "2") (pinfunction "Vout_2") (pintype "unspecified"))
      (node (ref "U9") (pin "8") (pinfunction "VDD_8") (pintype "unspecified"))
      (node (ref "UART") (pin "5") (pinfunction "VCC_5") (pintype "unspecified"))
      (node (ref "UART") (pin "8") (pinfunction "V3_8") (pintype "unspecified"))
      (node (ref "W-Link") (pin "1") (pinfunction "1_1") (pintype "input"))
    )
    (net (code "2") (name "+5V") (class "Default")
      (node (ref "C38") (pin "2") (pinfunction "2_2") (pintype "input"))
      (node (ref "U8") (pin "3") (pinfunction "Vin_3") (pintype "unspecified"))
      (node (ref "USB") (pin "A4B9") (pinfunction "VBUS_A4B9") (pintype "unspecified"))
      (node (ref "USB") (pin "B4A9") (pinfunction "VBUS_B4A9") (pintype "unspecified"))
    )
    (net (code "3") (name "+12V") (class "Default")
      (node (ref "C12") (pin "1") (pinfunction "1_1") (pintype "unspecified"))
      (node (ref "C14") (pin "2") (pinfunction "2_2") (pintype "unspecified"))
      (node (ref "C17") (pin "2") (pinfunction "2_2") (pintype "unspecified"))
      (node (ref "C19") (pin "2") (pinfunction "2_2") (pintype "unspecified"))
      (node (ref "C78") (pin "1") (pinfunction "1_1") (pintype "input"))
      (node (ref "C79") (pin "1") (pinfunction "1_1") (pintype "unspecified"))
      (node (ref "CN") (pin "1") (pinfunction "1_1") (pintype "input"))
      (node (ref "DC-DC") (pin "2") (pinfunction "EN_2") (pintype "unspecified"))
      (node (ref "DC-DC") (pin "3") (pinfunction "VIN_3") (pintype "unspecified"))
      (node (ref "Q1") (pin "5") (pinfunction "D_5") (pintype "unspecified"))
      (node (ref "Q1") (pin "6") (pinfunction "D_6") (pintype "unspecified"))
      (node (ref "Q1") (pin "7") (pinfunction "D_7") (pintype "unspecified"))
      (node (ref "Q1") (pin "8") (pinfunction "D_8") (pintype "unspecified"))
      (node (ref "Q2") (pin "5") (pinfunction "D_5") (pintype "unspecified"))
      (node (ref "Q2") (pin "6") (pinfunction "D_6") (pintype "unspecified"))
      (node (ref "Q2") (pin "7") (pinfunction "D_7") (pintype "unspecified"))
      (node (ref "Q2") (pin "8") (pinfunction "D_8") (pintype "unspecified"))
      (node (ref "Q3") (pin "5") (pinfunction "D_5") (pintype "unspecified"))
      (node (ref "Q3") (pin "6") (pinfunction "D_6") (pintype "unspecified"))
      (node (ref "Q3") (pin "7") (pinfunction "D_7") (pintype "unspecified"))
      (node (ref "Q3") (pin "8") (pinfunction "D_8") (pintype "unspecified"))
      (node (ref "U10") (pin "2") (pinfunction "A_2") (pintype "unspecified"))
      (node (ref "U11") (pin "1") (pinfunction "VCC_1") (pintype "unspecified"))
      (node (ref "U12") (pin "2") (pinfunction "A_2") (pintype "unspecified"))
      (node (ref "U13") (pin "1") (pinfunction "VCC_1") (pintype "unspecified"))
      (node (ref "U14") (pin "2") (pinfunction "A_2") (pintype "unspecified"))
      (node (ref "U6") (pin "1") (pinfunction "VCC_1") (pintype "unspecified"))
    )
    (net (code "4") (name "/A") (class "Default")
      (node (ref "C31") (pin "1") (pinfunction "1_1") (pintype "unspecified"))
      (node (ref "Q1") (pin "1") (pinfunction "S_1") (pintype "unspecified"))
      (node (ref "Q1") (pin "2") (pinfunction "S_2") (pintype "unspecified"))
      (node (ref "Q1") (pin "3") (pinfunction "S_3") (pintype "unspecified"))
      (node (ref "Q4") (pin "5") (pinfunction "D_5") (pintype "unspecified"))
      (node (ref "Q4") (pin "6") (pinfunction "D_6") (pintype "unspecified"))
      (node (ref "Q4") (pin "7") (pinfunction "D_7") (pintype "unspecified"))
      (node (ref "Q4") (pin "8") (pinfunction "D_8") (pintype "unspecified"))
      (node (ref "R3") (pin "1") (pinfunction "1_1") (pintype "input"))
      (node (ref "U6") (pin "6") (pinfunction "VS_6") (pintype "unspecified"))
      (node (ref "UVW") (pin "1") (pinfunction "1_1") (pintype "input"))
    )
    (net (code "5") (name "/ADC_A") (class "Default")
      (node (ref "U34") (pin "8") (pinfunction "OUT_8") (pintype "unspecified"))
      (node (ref "U39") (pin "21") (pinfunction "PB1A/DC9_21") (pintype "unspecified"))
    )
    (net (code "6") (name "/ADC_B") (class "Default")
      (node (ref "U35") (pin "8") (pinfunction "OUT_8") (pintype "unspecified"))
      (node (ref "U39") (pin "20") (pinfunction "PB0A/DC8_20") (pintype "unspecified"))
    )
    (net (code "7") (name "/B") (class "Default")
      (node (ref "C32") (pin "1") (pinfunction "1_1") (pintype "unspecified"))
      (node (ref "Q2") (pin "1") (pinfunction "S_1") (pintype "unspecified"))
      (node (ref "Q2") (pin "2") (pinfunction "S_2") (pintype "unspecified"))
      (node (ref "Q2") (pin "3") (pinfunction "S_3") (pintype "unspecified"))
      (node (ref "Q5") (pin "5") (pinfunction "D_5") (pintype "unspecified"))
      (node (ref "Q5") (pin "6") (pinfunction "D_6") (pintype "unspecified"))
      (node (ref "Q5") (pin "7") (pinfunction "D_7") (pintype "unspecified"))
      (node (ref "Q5") (pin "8") (pinfunction "D_8") (pintype "unspecified"))
      (node (ref "R4") (pin "1") (pinfunction "1_1") (pintype "input"))
      (node (ref "U11") (pin "6") (pinfunction "VS_6") (pintype "unspecified"))
      (node (ref "UVW") (pin "2") (pinfunction "2_2") (pintype "input"))
    )
    (net (code "8") (name "/C") (class "Default")
      (node (ref "C33") (pin "1") (pinfunction "1_1") (pintype "unspecified"))
      (node (ref "Q3") (pin "1") (pinfunction "S_1") (pintype "unspecified"))
      (node (ref "Q3") (pin "2") (pinfunction "S_2") (pintype "unspecified"))
      (node (ref "Q3") (pin "3") (pinfunction "S_3") (pintype "unspecified"))
      (node (ref "Q6") (pin "5") (pinfunction "D_5") (pintype "unspecified"))
      (node (ref "Q6") (pin "6") (pinfunction "D_6") (pintype "unspecified"))
      (node (ref "Q6") (pin "7") (pinfunction "D_7") (pintype "unspecified"))
      (node (ref "Q6") (pin "8") (pinfunction "D_8") (pintype "unspecified"))
      (node (ref "R5") (pin "1") (pinfunction "1_1") (pintype "input"))
      (node (ref "U13") (pin "6") (pinfunction "VS_6") (pintype "unspecified"))
      (node (ref "UVW") (pin "3") (pinfunction "3_3") (pintype "input"))
    )
    (net (code "9") (name "/CAN2_RX") (class "Default")
      (node (ref "CAN") (pin "4") (pinfunction "R_4") (pintype "unspecified"))
      (node (ref "U39") (pin "42") (pinfunction "PB5_42") (pintype "unspecified"))
    )
    (net (code "10") (name "/CAN2_TX") (class "Default")
      (node (ref "CAN") (pin "1") (pinfunction "D_1") (pintype "unspecified"))
      (node (ref "U39") (pin "43") (pinfunction "PB6/USB2DM_43") (pintype "unspecified"))
    )
    (net (code "11") (name "/D+") (class "Default")
      (node (ref "UART") (pin "1") (pinfunction "UD+_1") (pintype "unspecified"))
      (node (ref "USB") (pin "A6") (pinfunction "DP1_A6") (pintype "unspecified"))
      (node (ref "USB") (pin "B6") (pinfunction "DP2_B6") (pintype "unspecified"))
    )
    (net (code "12") (name "/D-") (class "Default")
      (node (ref "UART") (pin "2") (pinfunction "UD-_2") (pintype "unspecified"))
      (node (ref "USB") (pin "A7") (pinfunction "DN1_A7") (pintype "unspecified"))
      (node (ref "USB") (pin "B7") (pinfunction "DN2_B7") (pintype "unspecified"))
    )
    (net (code "13") (name "/I_A") (class "Default")
      (node (ref "Q4") (pin "1") (pinfunction "S_1") (pintype "unspecified"))
      (node (ref "Q4") (pin "2") (pinfunction "S_2") (pintype "unspecified"))
      (node (ref "Q4") (pin "3") (pinfunction "S_3") (pintype "unspecified"))
      (node (ref "R6") (pin "1") (pinfunction "1_1") (pintype "input"))
      (node (ref "R63") (pin "2") (pinfunction "2_2") (pintype "unspecified"))
      (node (ref "U34") (pin "2") (pinfunction "IN+_2") (pintype "unspecified"))
    )
    (net (code "14") (name "/I_B") (class "Default")
      (node (ref "Q5") (pin "1") (pinfunction "S_1") (pintype "unspecified"))
      (node (ref "Q5") (pin "2") (pinfunction "S_2") (pintype "unspecified"))
      (node (ref "Q5") (pin "3") (pinfunction "S_3") (pintype "unspecified"))
      (node (ref "R34") (pin "2") (pinfunction "2_2") (pintype "unspecified"))
      (node (ref "R7") (pin "1") (pinfunction "1_1") (pintype "input"))
      (node (ref "U35") (pin "2") (pinfunction "IN+_2") (pintype "unspecified"))
    )
    (net (code "15") (name "/KEY1") (class "Default")
      (node (ref "C80") (pin "1") (pinfunction "1_1") (pintype "unspecified"))
      (node (ref "SW2") (pin "2") (pinfunction "2_2") (pintype "unspecified"))
      (node (ref "U39") (pin "18") (pinfunction "PC4A/DC14_18") (pintype "unspecified"))
    )
    (net (code "16") (name "/KEY2") (class "Default")
      (node (ref "C86") (pin "1") (pinfunction "1_1") (pintype "unspecified"))
      (node (ref "SW3") (pin "2") (pinfunction "2_2") (pintype "unspecified"))
      (node (ref "U39") (pin "30") (pinfunction "PB15_30") (pintype "unspecified"))
    )
    (net (code "17") (name "/LED") (class "Default")
      (node (ref "R61") (pin "1") (pinfunction "1_1") (pintype "input"))
      (node (ref "U39") (pin "36") (pinfunction "PA12/USB1DP_36") (pintype "unspecified"))
    )
    (net (code "18") (name "/MOS_AH") (class "Default")
      (node (ref "D2") (pin "2") (pinfunction "A_2") (pintype "unspecified"))
      (node (ref "Q1") (pin "4") (pinfunction "G_4") (pintype "unspecified"))
      (node (ref "R12") (pin "2") (pinfunction "2_2") (pintype "unspecified"))
      (node (ref "R3") (pin "2") (pinfunction "2_2") (pintype "input"))
    )
    (net (code "19") (name "/MOS_AL") (class "Default")
      (node (ref "D1") (pin "2") (pinfunction "A_2") (pintype "unspecified"))
      (node (ref "Q4") (pin "4") (pinfunction "G_4") (pintype "unspecified"))
      (node (ref "R11") (pin "2") (pinfunction "2_2") (pintype "unspecified"))
      (node (ref "R6") (pin "2") (pinfunction "2_2") (pintype "input"))
    )
    (net (code "20") (name "/MOS_BH") (class "Default")
      (node (ref "D4") (pin "2") (pinfunction "A_2") (pintype "unspecified"))
      (node (ref "Q2") (pin "4") (pinfunction "G_4") (pintype "unspecified"))
      (node (ref "R14") (pin "2") (pinfunction "2_2") (pintype "unspecified"))
      (node (ref "R4") (pin "2") (pinfunction "2_2") (pintype "input"))
    )
    (net (code "21") (name "/MOS_BL") (class "Default")
      (node (ref "D3") (pin "2") (pinfunction "A_2") (pintype "unspecified"))
      (node (ref "Q5") (pin "4") (pinfunction "G_4") (pintype "unspecified"))
      (node (ref "R13") (pin "2") (pinfunction "2_2") (pintype "unspecified"))
      (node (ref "R7") (pin "2") (pinfunction "2_2") (pintype "input"))
    )
    (net (code "22") (name "/MOS_CH") (class "Default")
      (node (ref "D6") (pin "2") (pinfunction "A_2") (pintype "unspecified"))
      (node (ref "Q3") (pin "4") (pinfunction "G_4") (pintype "unspecified"))
      (node (ref "R16") (pin "2") (pinfunction "2_2") (pintype "unspecified"))
      (node (ref "R5") (pin "2") (pinfunction "2_2") (pintype "input"))
    )
    (net (code "23") (name "/MOS_CL") (class "Default")
      (node (ref "D5") (pin "2") (pinfunction "A_2") (pintype "unspecified"))
      (node (ref "Q6") (pin "4") (pinfunction "G_4") (pintype "unspecified"))
      (node (ref "R15") (pin "2") (pinfunction "2_2") (pintype "unspecified"))
      (node (ref "R8") (pin "2") (pinfunction "2_2") (pintype "input"))
    )
    (net (code "24") (name "/OSC-IN") (class "Default")
      (node (ref "C76") (pin "1") (pinfunction "1_1") (pintype "input"))
      (node (ref "U39") (pin "1") (pinfunction "OSC_IN/PD0_1") (pintype "unspecified"))
      (node (ref "X1") (pin "1") (pinfunction "IN_1") (pintype "unspecified"))
    )
    (net (code "25") (name "/OSC-OUT") (class "Default")
      (node (ref "C77") (pin "1") (pinfunction "1_1") (pintype "input"))
      (node (ref "U39") (pin "2") (pinfunction "OSC_OUT/PD1_2") (pintype "unspecified"))
      (node (ref "X1") (pin "3") (pinfunction "OUT_3") (pintype "unspecified"))
    )
    (net (code "26") (name "/PWM-A") (class "Default")
      (node (ref "U39") (pin "32") (pinfunction "PA8_32") (pintype "unspecified"))
      (node (ref "U6") (pin "2") (pinfunction "IN_2") (pintype "unspecified"))
    )
    (net (code "27") (name "/PWM-B") (class "Default")
      (node (ref "U11") (pin "2") (pinfunction "IN_2") (pintype "unspecified"))
      (node (ref "U39") (pin "34") (pinfunction "PA10_34") (pintype "unspecified"))
    )
    (net (code "28") (name "/PWM-C") (class "Default")
      (node (ref "U13") (pin "2") (pinfunction "IN_2") (pintype "unspecified"))
      (node (ref "U39") (pin "33") (pinfunction "PA9_33") (pintype "unspecified"))
    )
    (net (code "29") (name "/RST") (class "Default")
      (node (ref "C57") (pin "2") (pinfunction "2_2") (pintype "unspecified"))
      (node (ref "R60") (pin "2") (pinfunction "2_2") (pintype "input"))
      (node (ref "SW1") (pin "1") (pinfunction "1_1") (pintype "unspecified"))
      (node (ref "U39") (pin "3") (pinfunction "NRST_3") (pintype "unspecified"))
    )
    (net (code "30") (name "/SD") (class "Default")
      (node (ref "U11") (pin "3") (pinfunction "SD#_3") (pintype "unspecified"))
      (node (ref "U13") (pin "3") (pinfunction "SD#_3") (pintype "unspecified"))
      (node (ref "U39") (pin "35") (pinfunction "PA11/USB1DM_35") (pintype "unspecified"))
      (node (ref "U6") (pin "3") (pinfunction "SD#_3") (pintype "unspecified"))
    )
    (net (code "31") (name "/SPI1_CS") (class "Default")
      (node (ref "U39") (pin "13") (pinfunction "PA3A/DC3_13") (pintype "unspecified"))
      (node (ref "U9") (pin "3") (pinfunction "CS_3") (pintype "unspecified"))
    )
    (net (code "32") (name "/SPI1_MISO") (class "Default")
      (node (ref "U39") (pin "16") (pinfunction "PA6A/DC6_16") (pintype "unspecified"))
      (node (ref "U9") (pin "4") (pinfunction "MISO_4") (pintype "unspecified"))
    )
    (net (code "33") (name "/SPI1_MOSI") (class "Default")
      (node (ref "U39") (pin "17") (pinfunction "PA7A/DC7_17") (pintype "unspecified"))
      (node (ref "U9") (pin "2") (pinfunction "MOSI_2") (pintype "unspecified"))
    )
    (net (code "34") (name "/SPI1_SCK") (class "Default")
      (node (ref "U39") (pin "15") (pinfunction "PA5/ADC5/DAC1_15") (pintype "unspecified"))
      (node (ref "U9") (pin "7") (pinfunction "SCLK_7") (pintype "unspecified"))
    )
    (net (code "35") (name "/UART6_TX") (class "Default")
      (node (ref "U39") (pin "45") (pinfunction "PB8_45") (pintype "unspecified"))
      (node (ref "UART") (pin "7") (pinfunction "RXD_7") (pintype "unspecified"))
    )
    (net (code "36") (name "/USART1_RX") (class "Default")
      (node (ref "U39") (pin "44") (pinfunction "PB7/USB2DP_44") (pintype "unspecified"))
      (node (ref "UART") (pin "6") (pinfunction "TXD_6") (pintype "unspecified"))
    )
    (net (code "37") (name "/WCLK") (class "Default")
      (node (ref "U39") (pin "38") (pinfunction "PA14S/WCLK_38") (pintype "unspecified"))
      (node (ref "W-Link") (pin "4") (pinfunction "4_4") (pintype "input"))
    )
    (net (code "38") (name "/WDIO") (class "Default")
      (node (ref "U39") (pin "37") (pinfunction "PA13S/WDIO_37") (pintype "unspecified"))
      (node (ref "W-Link") (pin "3") (pinfunction "3_3") (pintype "input"))
    )
    (net (code "39") (name "AGND") (class "Default")
      (node (ref "C78") (pin "2") (pinfunction "2_2") (pintype "input"))
      (node (ref "C79") (pin "2") (pinfunction "2_2") (pintype "unspecified"))
      (node (ref "CN") (pin "2") (pinfunction "2_2") (pintype "input"))
      (node (ref "Q6") (pin "1") (pinfunction "S_1") (pintype "unspecified"))
      (node (ref "Q6") (pin "2") (pinfunction "S_2") (pintype "unspecified"))
      (node (ref "Q6") (pin "3") (pinfunction "S_3") (pintype "unspecified"))
      (node (ref "R34") (pin "1") (pinfunction "1_1") (pintype "unspecified"))
      (node (ref "R59") (pin "2") (pinfunction "2_2") (pintype "input"))
      (node (ref "R63") (pin "1") (pinfunction "1_1") (pintype "unspecified"))
      (node (ref "R8") (pin "1") (pinfunction "1_1") (pintype "input"))
      (node (ref "U34") (pin "3") (pinfunction "IN-_3") (pintype "unspecified"))
      (node (ref "U35") (pin "3") (pinfunction "IN-_3") (pintype "unspecified"))
    )
    (net (code "40") (name "GND") (class "Default")
      (node (ref "C10") (pin "2") (pinfunction "2_2") (pintype "unspecified"))
      (node (ref "C12") (pin "2") (pinfunction "2_2") (pintype "unspecified"))
      (node (ref "C14") (pin "1") (pinfunction "1_1") (pintype "unspecified"))
      (node (ref "C15") (pin "1") (pinfunction "1_1") (pintype "unspecified"))
      (node (ref "C17") (pin "1") (pinfunction "1_1") (pintype "unspecified"))
      (node (ref "C19") (pin "1") (pinfunction "1_1") (pintype "unspecified"))
      (node (ref "C37") (pin "1") (pinfunction "1_1") (pintype "input"))
      (node (ref "C38") (pin "1") (pinfunction "1_1") (pintype "input"))
      (node (ref "C57") (pin "1") (pinfunction "1_1") (pintype "unspecified"))
      (node (ref "C64") (pin "2") (pinfunction "2_2") (pintype "unspecified"))
      (node (ref "C65") (pin "2") (pinfunction "2_2") (pintype "unspecified"))
      (node (ref "C73") (pin "1") (pinfunction "1_1") (pintype "unspecified"))
      (node (ref "C74") (pin "1") (pinfunction "1_1") (pintype "unspecified"))
      (node (ref "C75") (pin "1") (pinfunction "1_1") (pintype "unspecified"))
      (node (ref "C76") (pin "2") (pinfunction "2_2") (pintype "input"))
      (node (ref "C77") (pin "2") (pinfunction "2_2") (pintype "input"))
      (node (ref "C81") (pin "1") (pinfunction "1_1") (pintype "unspecified"))
      (node (ref "C82") (pin "1") (pinfunction "1_1") (pintype "unspecified"))
      (node (ref "C85") (pin "1") (pinfunction "1_1") (pintype "unspecified"))
      (node (ref "C86") (pin "2") (pinfunction "2_2") (pintype "unspecified"))
      (node (ref "C9") (pin "2") (pinfunction "2_2") (pintype "unspecified"))
      (node (ref "CAN") (pin "2") (pinfunction "GND_2") (pintype "unspecified"))
      (node (ref "DC-DC") (pin "4") (pinfunction "GND_4") (pintype "unspecified"))
      (node (ref "R57") (pin "2") (pinfunction "2_2") (pintype "input"))
      (node (ref "R59") (pin "1") (pinfunction "1_1") (pintype "input"))
      (node (ref "SW1") (pin "2") (pinfunction "2_2") (pintype "unspecified"))
      (node (ref "SW3") (pin "1") (pinfunction "1_1") (pintype "unspecified"))
      (node (ref "U11") (pin "4") (pinfunction "GND_4") (pintype "unspecified"))
      (node (ref "U13") (pin "4") (pinfunction "GND_4") (pintype "unspecified"))
      (node (ref "U28") (pin "1") (pinfunction "K_1") (pintype "unspecified"))
      (node (ref "U34") (pin "1") (pinfunction "NC_1") (pintype "unspecified"))
      (node (ref "U34") (pin "4") (pinfunction "GND_4") (pintype "unspecified"))
      (node (ref "U34") (pin "7") (pinfunction "REF1_7") (pintype "unspecified"))
      (node (ref "U35") (pin "1") (pinfunction "NC_1") (pintype "unspecified"))
      (node (ref "U35") (pin "4") (pinfunction "GND_4") (pintype "unspecified"))
      (node (ref "U35") (pin "7") (pinfunction "REF1_7") (pintype "unspecified"))
      (node (ref "U39") (pin "26") (pinfunction "VSS_1_26") (pintype "unspecified"))
      (node (ref "U39") (pin "47") (pinfunction "VSS_3_47") (pintype "unspecified"))
      (node (ref "U39") (pin "8") (pinfunction "VSSA_8") (pintype "unspecified"))
      (node (ref "U6") (pin "4") (pinfunction "GND_4") (pintype "unspecified"))
      (node (ref "U8") (pin "1") (pinfunction "GND_1") (pintype "unspecified"))
      (node (ref "U9") (pin "5") (pinfunction "GND_5") (pintype "unspecified"))
      (node (ref "UART") (pin "3") (pinfunction "GND_3") (pintype "unspecified"))
      (node (ref "USB") (pin "1") (pinfunction "SHELL_1") (pintype "unspecified"))
      (node (ref "USB") (pin "2") (pinfunction "SHELL_2") (pintype "unspecified"))
      (node (ref "USB") (pin "3") (pinfunction "SHELL_3") (pintype "unspecified"))
      (node (ref "USB") (pin "4") (pinfunction "SHELL_4") (pintype "unspecified"))
      (node (ref "USB") (pin "A1B12") (pinfunction "GND_A1B12") (pintype "unspecified"))
      (node (ref "USB") (pin "B1A12") (pinfunction "GND_B1A12") (pintype "unspecified"))
      (node (ref "W-Link") (pin "2") (pinfunction "2_2") (pintype "input"))
      (node (ref "X1") (pin "2") (pinfunction "GND_2") (pintype "unspecified"))
    )
    (net (code "41") (name "Net-(CAN-CANH)") (class "Default")
      (node (ref "CAN") (pin "7") (pinfunction "CANH_7") (pintype "unspecified"))
      (node (ref "R58") (pin "1") (pinfunction "1_1") (pintype "unspecified"))
      (node (ref "U38") (pin "1") (pinfunction "1_1") (pintype "unspecified"))
    )
    (net (code "42") (name "Net-(CAN-CANL)") (class "Default")
      (node (ref "CAN") (pin "6") (pinfunction "CANL_6") (pintype "unspecified"))
      (node (ref "MODE1") (pin "2") (pinfunction "2_2") (pintype "unspecified"))
      (node (ref "U38") (pin "2") (pinfunction "2_2") (pintype "unspecified"))
    )
    (net (code "43") (name "Net-(CAN-RS)") (class "Default")
      (node (ref "CAN") (pin "8") (pinfunction "RS_8") (pintype "unspecified"))
      (node (ref "R57") (pin "1") (pinfunction "1_1") (pintype "input"))
    )
    (net (code "44") (name "Net-(D1-c)") (class "Default")
      (node (ref "D1") (pin "1") (pinfunction "c_1") (pintype "unspecified"))
      (node (ref "R11") (pin "1") (pinfunction "1_1") (pintype "unspecified"))
      (node (ref "U6") (pin "5") (pinfunction "LO_5") (pintype "unspecified"))
    )
    (net (code "45") (name "Net-(D2-c)") (class "Default")
      (node (ref "D2") (pin "1") (pinfunction "c_1") (pintype "unspecified"))
      (node (ref "R12") (pin "1") (pinfunction "1_1") (pintype "unspecified"))
      (node (ref "U6") (pin "7") (pinfunction "HO_7") (pintype "unspecified"))
    )
    (net (code "46") (name "Net-(D3-c)") (class "Default")
      (node (ref "D3") (pin "1") (pinfunction "c_1") (pintype "unspecified"))
      (node (ref "R13") (pin "1") (pinfunction "1_1") (pintype "unspecified"))
      (node (ref "U11") (pin "5") (pinfunction "LO_5") (pintype "unspecified"))
    )
    (net (code "47") (name "Net-(D4-c)") (class "Default")
      (node (ref "D4") (pin "1") (pinfunction "c_1") (pintype "unspecified"))
      (node (ref "R14") (pin "1") (pinfunction "1_1") (pintype "unspecified"))
      (node (ref "U11") (pin "7") (pinfunction "HO_7") (pintype "unspecified"))
    )
    (net (code "48") (name "Net-(D5-c)") (class "Default")
      (node (ref "D5") (pin "1") (pinfunction "c_1") (pintype "unspecified"))
      (node (ref "R15") (pin "1") (pinfunction "1_1") (pintype "unspecified"))
      (node (ref "U13") (pin "5") (pinfunction "LO_5") (pintype "unspecified"))
    )
    (net (code "49") (name "Net-(D6-c)") (class "Default")
      (node (ref "D6") (pin "1") (pinfunction "c_1") (pintype "unspecified"))
      (node (ref "R16") (pin "1") (pinfunction "1_1") (pintype "unspecified"))
      (node (ref "U13") (pin "7") (pinfunction "HO_7") (pintype "unspecified"))
    )
    (net (code "50") (name "Net-(DC-DC-BST)") (class "Default")
      (node (ref "C11") (pin "2") (pinfunction "2_2") (pintype "unspecified"))
      (node (ref "DC-DC") (pin "6") (pinfunction "BST_6") (pintype "unspecified"))
    )
    (net (code "51") (name "Net-(DC-DC-SW)") (class "Default")
      (node (ref "C11") (pin "1") (pinfunction "1_1") (pintype "unspecified"))
      (node (ref "DC-DC") (pin "5") (pinfunction "SW_5") (pintype "unspecified"))
      (node (ref "L2") (pin "1") (pinfunction "1_1") (pintype "unspecified"))
    )
    (net (code "52") (name "Net-(MODE1-Pad1)") (class "Default")
      (node (ref "MODE1") (pin "1") (pinfunction "1_1") (pintype "unspecified"))
      (node (ref "R58") (pin "2") (pinfunction "2_2") (pintype "unspecified"))
    )
    (net (code "53") (name "Net-(U10-K)") (class "Default")
      (node (ref "C31") (pin "2") (pinfunction "2_2") (pintype "unspecified"))
      (node (ref "U10") (pin "1") (pinfunction "K_1") (pintype "unspecified"))
      (node (ref "U6") (pin "8") (pinfunction "VB_8") (pintype "unspecified"))
    )
    (net (code "54") (name "Net-(U11-VB)") (class "Default")
      (node (ref "C32") (pin "2") (pinfunction "2_2") (pintype "unspecified"))
      (node (ref "U11") (pin "8") (pinfunction "VB_8") (pintype "unspecified"))
      (node (ref "U12") (pin "1") (pinfunction "K_1") (pintype "unspecified"))
    )
    (net (code "55") (name "Net-(U13-VB)") (class "Default")
      (node (ref "C33") (pin "2") (pinfunction "2_2") (pintype "unspecified"))
      (node (ref "U13") (pin "8") (pinfunction "VB_8") (pintype "unspecified"))
      (node (ref "U14") (pin "1") (pinfunction "K_1") (pintype "unspecified"))
    )
    (net (code "56") (name "Net-(U28-A)") (class "Default")
      (node (ref "R61") (pin "2") (pinfunction "2_2") (pintype "input"))
      (node (ref "U28") (pin "2") (pinfunction "A_2") (pintype "unspecified"))
    )
    (net (code "57") (name "unconnected-(CAN-VREF-Pad5)") (class "Default")
      (node (ref "CAN") (pin "5") (pinfunction "VREF_5") (pintype "unspecified+no_connect"))
    )
    (net (code "58") (name "unconnected-(CN-Pad3)") (class "Default")
      (node (ref "CN") (pin "3") (pinfunction "3_3") (pintype "input+no_connect"))
    )
    (net (code "59") (name "unconnected-(CN-Pad4)") (class "Default")
      (node (ref "CN") (pin "4") (pinfunction "4_4") (pintype "input+no_connect"))
    )
    (net (code "60") (name "unconnected-(MODE1-Pad3)") (class "Default")
      (node (ref "MODE1") (pin "3") (pinfunction "3_3") (pintype "unspecified+no_connect"))
    )
    (net (code "61") (name "unconnected-(MODE1-Pad4)") (class "Default")
      (node (ref "MODE1") (pin "4") (pinfunction "4_4") (pintype "unspecified+no_connect"))
    )
    (net (code "62") (name "unconnected-(U9-PWM-Pad6)") (class "Default")
      (node (ref "U9") (pin "6") (pinfunction "PWM_6") (pintype "unspecified+no_connect"))
    )
    (net (code "63") (name "unconnected-(U9-TEST-Pad1)") (class "Default")
      (node (ref "U9") (pin "1") (pinfunction "TEST_1") (pintype "unspecified+no_connect"))
    )
    (net (code "64") (name "unconnected-(U38-Pad3)") (class "Default")
      (node (ref "U38") (pin "3") (pinfunction "3_3") (pintype "unspecified+no_connect"))
    )
    (net (code "65") (name "unconnected-(U38-Pad4)") (class "Default")
      (node (ref "U38") (pin "4") (pinfunction "4_4") (pintype "unspecified+no_connect"))
    )
    (net (code "66") (name "unconnected-(U39-PA0{slash}WKUP{slash}ADC0-Pad10)") (class "Default")
      (node (ref "U39") (pin "10") (pinfunction "PA0/WKUP/ADC0_10") (pintype "unspecified+no_connect"))
    )
    (net (code "67") (name "unconnected-(U39-PA1{slash}ADC1-Pad11)") (class "Default")
      (node (ref "U39") (pin "11") (pinfunction "PA1/ADC1_11") (pintype "unspecified+no_connect"))
    )
    (net (code "68") (name "unconnected-(U39-PA2{slash}ADC2-Pad12)") (class "Default")
      (node (ref "U39") (pin "12") (pinfunction "PA2/ADC2_12") (pintype "unspecified+no_connect"))
    )
    (net (code "69") (name "unconnected-(U39-PA4A{slash}DC4{slash}DAC0-Pad14)") (class "Default")
      (node (ref "U39") (pin "14") (pinfunction "PA4A/DC4/DAC0_14") (pintype "unspecified+no_connect"))
    )
    (net (code "70") (name "unconnected-(U39-PA15-Pad39)") (class "Default")
      (node (ref "U39") (pin "39") (pinfunction "PA15_39") (pintype "unspecified+no_connect"))
    )
    (net (code "71") (name "unconnected-(U39-PB2-Pad22)") (class "Default")
      (node (ref "U39") (pin "22") (pinfunction "PB2_22") (pintype "unspecified+no_connect"))
    )
    (net (code "72") (name "unconnected-(U39-PB3-Pad40)") (class "Default")
      (node (ref "U39") (pin "40") (pinfunction "PB3_40") (pintype "unspecified+no_connect"))
    )
    (net (code "73") (name "unconnected-(U39-PB4-Pad41)") (class "Default")
      (node (ref "U39") (pin "41") (pinfunction "PB4_41") (pintype "unspecified+no_connect"))
    )
    (net (code "74") (name "unconnected-(U39-PB9-Pad46)") (class "Default")
      (node (ref "U39") (pin "46") (pinfunction "PB9_46") (pintype "unspecified+no_connect"))
    )
    (net (code "75") (name "unconnected-(U39-PB10-Pad23)") (class "Default")
      (node (ref "U39") (pin "23") (pinfunction "PB10_23") (pintype "unspecified+no_connect"))
    )
    (net (code "76") (name "unconnected-(U39-PB11-Pad24)") (class "Default")
      (node (ref "U39") (pin "24") (pinfunction "PB11_24") (pintype "unspecified+no_connect"))
    )
    (net (code "77") (name "unconnected-(U39-PB12-Pad27)") (class "Default")
      (node (ref "U39") (pin "27") (pinfunction "PB12_27") (pintype "unspecified+no_connect"))
    )
    (net (code "78") (name "unconnected-(U39-PB13-Pad28)") (class "Default")
      (node (ref "U39") (pin "28") (pinfunction "PB13_28") (pintype "unspecified+no_connect"))
    )
    (net (code "79") (name "unconnected-(U39-PB14-Pad29)") (class "Default")
      (node (ref "U39") (pin "29") (pinfunction "PB14_29") (pintype "unspecified+no_connect"))
    )
    (net (code "80") (name "unconnected-(U39-PC0{slash}ADC10-Pad4)") (class "Default")
      (node (ref "U39") (pin "4") (pinfunction "PC0/ADC10_4") (pintype "unspecified+no_connect"))
    )
    (net (code "81") (name "unconnected-(U39-PC1{slash}ADC11-Pad5)") (class "Default")
      (node (ref "U39") (pin "5") (pinfunction "PC1/ADC11_5") (pintype "unspecified+no_connect"))
    )
    (net (code "82") (name "unconnected-(U39-PC2{slash}ADC12-Pad6)") (class "Default")
      (node (ref "U39") (pin "6") (pinfunction "PC2/ADC12_6") (pintype "unspecified+no_connect"))
    )
    (net (code "83") (name "unconnected-(U39-PC3{slash}ADC13-Pad7)") (class "Default")
      (node (ref "U39") (pin "7") (pinfunction "PC3/ADC13_7") (pintype "unspecified+no_connect"))
    )
    (net (code "84") (name "unconnected-(U39-PC5A{slash}DC15-Pad19)") (class "Default")
      (node (ref "U39") (pin "19") (pinfunction "PC5A/DC15_19") (pintype "unspecified+no_connect"))
    )
    (net (code "85") (name "unconnected-(U39-PC6-Pad31)") (class "Default")
      (node (ref "U39") (pin "31") (pinfunction "PC6_31") (pintype "unspecified+no_connect"))
    )
    (net (code "86") (name "unconnected-(UART-RTS#-Pad4)") (class "Default")
      (node (ref "UART") (pin "4") (pinfunction "RTS#_4") (pintype "unspecified+no_connect"))
    )
    (net (code "87") (name "unconnected-(USB-CC1-PadA5)") (class "Default")
      (node (ref "USB") (pin "A5") (pinfunction "CC1_A5") (pintype "unspecified+no_connect"))
    )
    (net (code "88") (name "unconnected-(USB-CC2-PadB5)") (class "Default")
      (node (ref "USB") (pin "B5") (pinfunction "CC2_B5") (pintype "unspecified+no_connect"))
    )
    (net (code "89") (name "unconnected-(USB-SBU1-PadA8)") (class "Default")
      (node (ref "USB") (pin "A8") (pinfunction "SBU1_A8") (pintype "unspecified+no_connect"))
    )
    (net (code "90") (name "unconnected-(USB-SBU2-PadB8)") (class "Default")
      (node (ref "USB") (pin "B8") (pinfunction "SBU2_B8") (pintype "unspecified+no_connect"))
    )
    (net (code "91") (name "unconnected-(UVW-Pad4)") (class "Default")
      (node (ref "UVW") (pin "4") (pinfunction "4_4") (pintype "input+no_connect"))
    )
    (net (code "92") (name "unconnected-(UVW-Pad5)") (class "Default")
      (node (ref "UVW") (pin "5") (pinfunction "5_5") (pintype "input+no_connect"))
    )
    (net (code "93") (name "unconnected-(W-Link-Pad5)") (class "Default")
      (node (ref "W-Link") (pin "5") (pinfunction "5_5") (pintype "input+no_connect"))
    )
    (net (code "94") (name "unconnected-(W-Link-Pad6)") (class "Default")
      (node (ref "W-Link") (pin "6") (pinfunction "6_6") (pintype "input+no_connect"))
    )
  )
)
